# Nametag.net
KiCad netlist of a schematic drawn in EAGLE
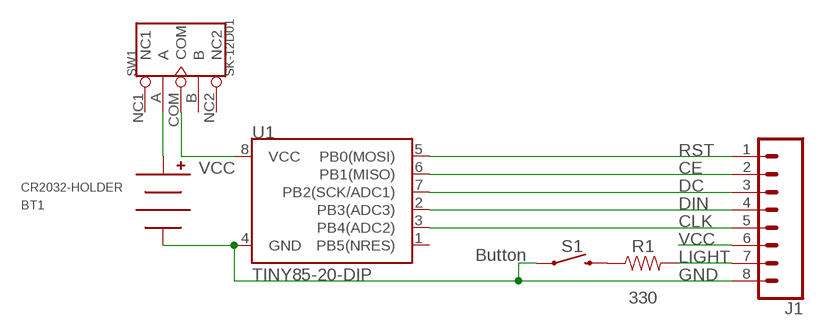
[diagram p0: schematic, sheet 1]

(export (version "E")
  (design (tool "Eeschema 10.0.6"))
  (components
    (comp (ref "BT1")
      (value "CR2032-HOLDER")
      (footprint "eagle-import:CH28-2032LF")
      (libsource (lib "eagle-import") (part "CR2032-HOLDER"))
    )
    (comp (ref "J1")
      (value "CONN_08\"")
      (footprint "eagle-import:1X08")
      (libsource (lib "eagle-import") (part "CONN_08{dblquote}"))
    )
    (comp (ref "R1")
      (value "330")
      (footprint "eagle-import:AXIAL-0.3")
      (libsource (lib "eagle-import") (part "330OHM-HORIZ-1/10W-5%"))
    )
    (comp (ref "S1")
      (value "Button")
      (footprint "eagle-import:TACTILE_SWITCH_PTH_6.0MM")
      (libsource (lib "eagle-import") (part "MOMENTARY-SWITCH-SPST-PTH-6.0MM"))
    )
    (comp (ref "SW1")
      (value "SK-12D01")
      (footprint "eagle-import:SW5-2.0-8.8X4.4X4.7MM-90D")
      (libsource (lib "eagle-import") (part "DIP-TOGGLE-SWITCH-ON-ON(3+2P-8.8X4.6MM)"))
    )
    (comp (ref "U1")
      (value "TINY85-20-DIP")
      (footprint "eagle-import:DIP08_MCU")
      (libsource (lib "eagle-import") (part "ATTINY45TINY85-20-DIP"))
    )
  )
  (nets
    (net (code "1") (name "/CE") (class "Default")
      (node (ref "J1") (pin "2") (pinfunction "2_2") (pintype "passive"))
      (node (ref "U1") (pin "6") (pinfunction "PB1(MISO)_6") (pintype "bidirectional"))
    )
    (net (code "2") (name "/CLK") (class "Default")
      (node (ref "J1") (pin "5") (pinfunction "5_5") (pintype "passive"))
      (node (ref "U1") (pin "3") (pinfunction "PB4(ADC2)_3") (pintype "bidirectional"))
    )
    (net (code "3") (name "/DC") (class "Default")
      (node (ref "J1") (pin "3") (pinfunction "3_3") (pintype "passive"))
      (node (ref "U1") (pin "7") (pinfunction "PB2(SCK/ADC1)_7") (pintype "bidirectional"))
    )
    (net (code "4") (name "/DIN") (class "Default")
      (node (ref "J1") (pin "4") (pinfunction "4_4") (pintype "passive"))
      (node (ref "U1") (pin "2") (pinfunction "PB3(ADC3)_2") (pintype "bidirectional"))
    )
    (net (code "5") (name "/GND") (class "Default")
      (node (ref "BT1") (pin "NEG") (pinfunction "NEG_NEG") (pintype "bidirectional"))
      (node (ref "J1") (pin "8") (pinfunction "8_8") (pintype "passive"))
      (node (ref "S1") (pin "1") (pinfunction "1_1") (pintype "passive"))
      (node (ref "U1") (pin "4") (pinfunction "GND_4") (pintype "bidirectional"))
    )
    (net (code "6") (name "/LIGHT") (class "Default")
      (node (ref "J1") (pin "7") (pinfunction "7_7") (pintype "passive"))
      (node (ref "R1") (pin "P$2") (pinfunction "2_P$2") (pintype "passive"))
    )
    (net (code "7") (name "/RST") (class "Default")
      (node (ref "J1") (pin "1") (pinfunction "1_1") (pintype "passive"))
      (node (ref "U1") (pin "5") (pinfunction "PB0(MOSI)_5") (pintype "bidirectional"))
    )
    (net (code "8") (name "/VCC") (class "Default")
      (node (ref "J1") (pin "6") (pinfunction "6_6") (pintype "passive"))
      (node (ref "SW1") (pin "COM") (pinfunction "COM_COM") (pintype "bidirectional"))
      (node (ref "U1") (pin "8") (pinfunction "VCC_8") (pintype "bidirectional"))
    )
    (net (code "9") (name "Net-(BT1-PadPOS)") (class "Default")
      (node (ref "BT1") (pin "POS") (pinfunction "POS_POS") (pintype "bidirectional"))
      (node (ref "SW1") (pin "A") (pinfunction "A_A") (pintype "bidirectional"))
    )
    (net (code "10") (name "Net-(R1-1)") (class "Default")
      (node (ref "R1") (pin "P$1") (pinfunction "1_P$1") (pintype "passive"))
      (node (ref "S1") (pin "3") (pinfunction "2_3") (pintype "passive"))
    )
    (net (code "11") (name "unconnected-(SW1-PadB)") (class "Default")
      (node (ref "SW1") (pin "B") (pinfunction "B_B") (pintype "bidirectional"))
    )
    (net (code "12") (name "unconnected-(SW1-PadNC1)") (class "Default")
      (node (ref "SW1") (pin "NC1") (pinfunction "NC1_NC1") (pintype "bidirectional"))
    )
    (net (code "13") (name "unconnected-(SW1-PadNC2)") (class "Default")
      (node (ref "SW1") (pin "NC2") (pinfunction "NC2_NC2") (pintype "bidirectional"))
    )
    (net (code "14") (name "unconnected-(U1-PB5(NRES)-Pad1)") (class "Default")
      (node (ref "U1") (pin "1") (pinfunction "PB5(NRES)_1") (pintype "bidirectional"))
    )
  )
)
